# 2019-NUC029LAN.net
KiCad netlist of a schematic drawn in Altium Designer
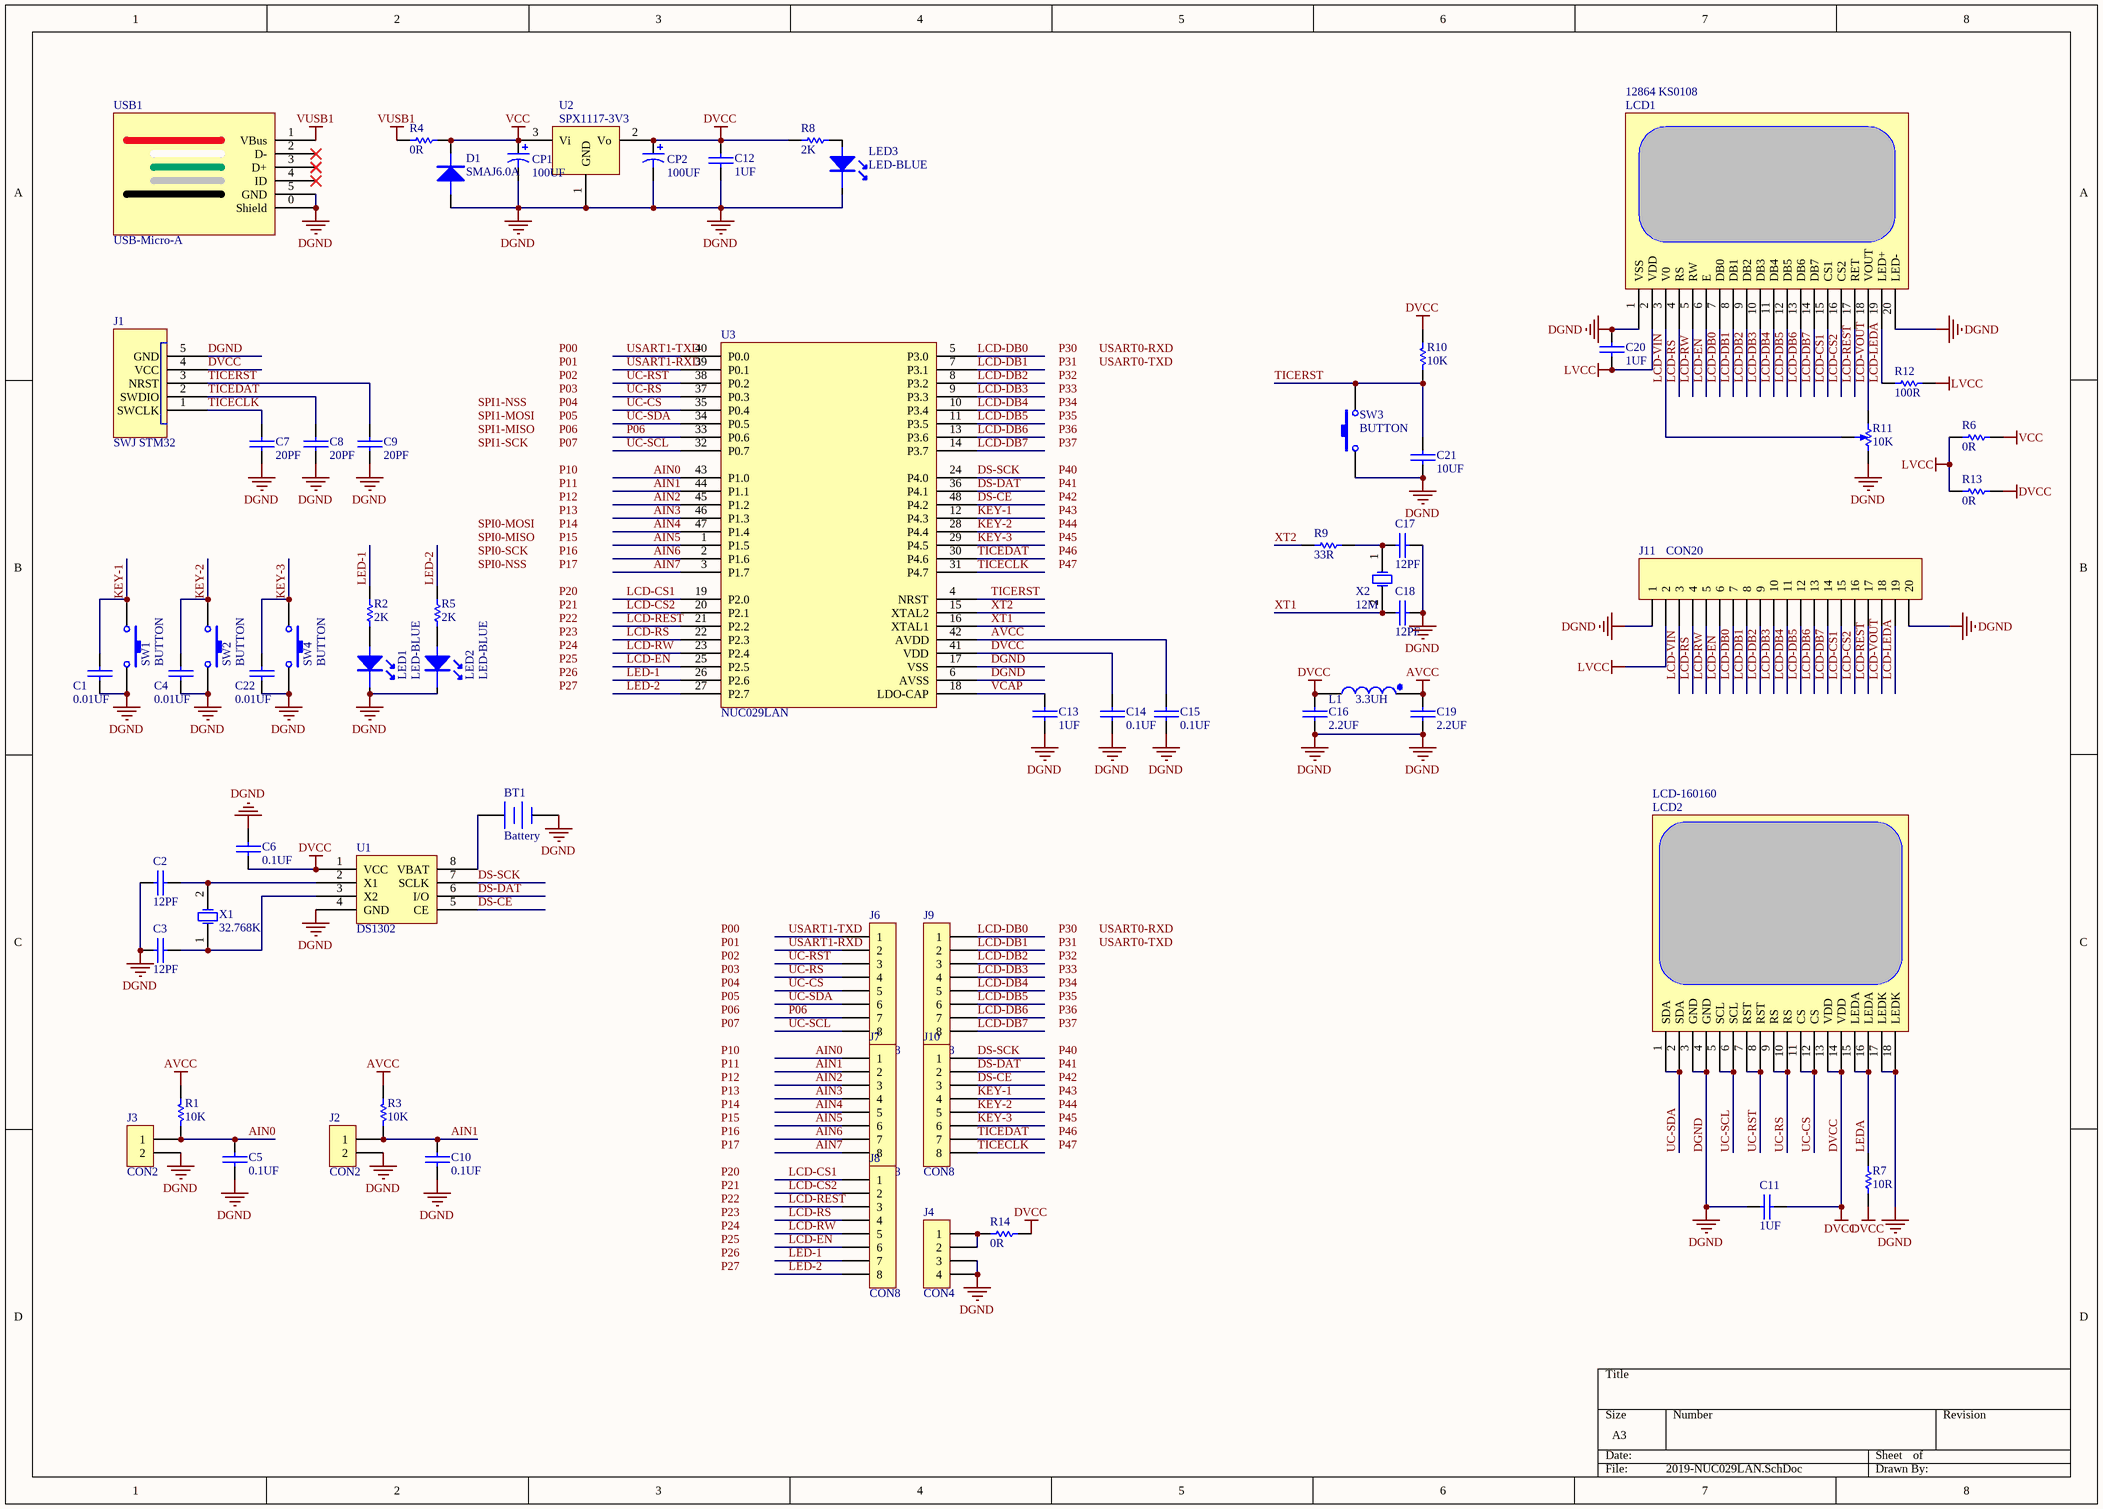
[diagram p0: 2019-NUC029LAN.SchDoc]

(export (version "E")
  (design (tool "Eeschema 10.0.6"))
  (components
    (comp (ref "BT1")
      (value "Battery")
      (footprint "cr1200")
      (description "Multicell Battery")
      (fields (field (name "PUBLISHER") "Altium Limited"))
      (libsource (lib "Miscellaneous Devices") (part "Battery"))
    )
    (comp (ref "C1") (value "0.01UF") (footprint "LC-0603-C") (libsource (lib "原理图库") (part "CAP")))
    (comp (ref "C2") (value "12PF") (footprint "LC-0603-C") (libsource (lib "原理图库") (part "CAP")))
    (comp (ref "C3") (value "12PF") (footprint "LC-0603-C") (libsource (lib "原理图库") (part "CAP")))
    (comp (ref "C4") (value "0.01UF") (footprint "LC-0603-C") (libsource (lib "原理图库") (part "CAP")))
    (comp (ref "C5") (value "0.1UF") (footprint "LC-0603-C") (libsource (lib "原理图库") (part "CAP")))
    (comp (ref "C6") (value "0.1UF") (footprint "LC-0603-C") (libsource (lib "原理图库") (part "CAP")))
    (comp (ref "C7") (value "20PF") (footprint "LC-0603-C") (libsource (lib "原理图库") (part "CAP")))
    (comp (ref "C8") (value "20PF") (footprint "LC-0603-C") (libsource (lib "原理图库") (part "CAP")))
    (comp (ref "C9") (value "20PF") (footprint "LC-0603-C") (libsource (lib "原理图库") (part "CAP")))
    (comp (ref "C10") (value "0.1UF") (footprint "LC-0603-C") (libsource (lib "原理图库") (part "CAP")))
    (comp (ref "C11") (value "1UF") (footprint "lc-0805-c") (libsource (lib "") (part "CAP_1")))
    (comp (ref "C12") (value "1UF") (footprint "lc-0805-c") (libsource (lib "") (part "CAP_1")))
    (comp (ref "C13") (value "1UF") (footprint "LC-0603-C") (libsource (lib "原理图库") (part "CAP")))
    (comp (ref "C14") (value "0.1UF") (footprint "LC-0603-C") (libsource (lib "原理图库") (part "CAP")))
    (comp (ref "C15") (value "0.1UF") (footprint "LC-0603-C") (libsource (lib "原理图库") (part "CAP")))
    (comp (ref "C16") (value "2.2UF") (footprint "LC-0603-C") (libsource (lib "原理图库") (part "CAP")))
    (comp (ref "C17") (value "12PF") (footprint "LC-0603-C") (libsource (lib "原理图库") (part "CAP")))
    (comp (ref "C18") (value "12PF") (footprint "LC-0603-C") (libsource (lib "原理图库") (part "CAP")))
    (comp (ref "C19") (value "2.2UF") (footprint "LC-0603-C") (libsource (lib "原理图库") (part "CAP")))
    (comp (ref "C20") (value "1UF") (footprint "lc-0805-c") (libsource (lib "") (part "CAP_1")))
    (comp (ref "C21") (value "10UF") (footprint "LC-0603-C") (libsource (lib "原理图库") (part "CAP")))
    (comp (ref "C22") (value "0.01UF") (footprint "LC-0603-C") (libsource (lib "原理图库") (part "CAP")))
    (comp (ref "CP1") (value "100UF") (footprint "LC-CASE-B_3528") (libsource (lib "原理图库") (part "CAP1")))
    (comp (ref "CP2") (value "100UF") (footprint "LC-CASE-B_3528") (libsource (lib "原理图库") (part "CAP1")))
    (comp (ref "D1")
      (value "SMAJ6.0A")
      (footprint "LC-SMA(DO-214AC)_S3")
      (libsource (lib "原理图库") (part "DIODE"))
    )
    (comp (ref "J1") (value "SWJ STM32") (footprint "ICD2") (libsource (lib "原理图库.坏") (part "SWJ")))
    (comp (ref "J2")
      (value "CON2")
      (footprint "lc-0805-L")
      (description "Connector")
      (libsource (lib "接插件") (part "CON2"))
    )
    (comp (ref "J3")
      (value "CON2")
      (footprint "lc-0805-L")
      (description "Connector")
      (libsource (lib "接插件") (part "CON2"))
    )
    (comp (ref "J4")
      (value "CON4")
      (footprint "sip-4")
      (description "Connector")
      (libsource (lib "接插件") (part "CON4"))
    )
    (comp (ref "J6")
      (value "CON8")
      (footprint "sip-8")
      (description "Connector")
      (libsource (lib "接插件") (part "CON8"))
    )
    (comp (ref "J7")
      (value "CON8")
      (footprint "sip-8")
      (description "Connector")
      (libsource (lib "接插件") (part "CON8"))
    )
    (comp (ref "J8")
      (value "CON8")
      (footprint "sip-8")
      (description "Connector")
      (libsource (lib "接插件") (part "CON8"))
    )
    (comp (ref "J9")
      (value "CON8")
      (footprint "sip-8")
      (description "Connector")
      (libsource (lib "") (part "CON8_1"))
    )
    (comp (ref "J10")
      (value "CON8")
      (footprint "sip-8")
      (description "Connector")
      (libsource (lib "") (part "CON8_1"))
    )
    (comp (ref "J11")
      (value "CON20")
      (footprint "sip-20")
      (description "Connector")
      (libsource (lib "接插件") (part "CON20"))
    )
    (comp (ref "L1") (value "3.3UH") (footprint "lc-0805-L") (libsource (lib "原理图库") (part "INDUCTOR")))
    (comp (ref "LCD1")
      (value "12864 KS0108")
      (footprint "12864 ks0108")
      (libsource (lib "原理图库.坏") (part "12864 KS0108"))
    )
    (comp (ref "LCD2")
      (value "LCD-160160")
      (footprint "lcd-160160")
      (libsource (lib "原理图库.坏") (part "LCD-160160"))
    )
    (comp (ref "LED1") (value "LED-BLUE") (footprint "LC-0805-LED") (libsource (lib "原理图库.坏") (part "LED")))
    (comp (ref "LED2") (value "LED-BLUE") (footprint "LC-0805-LED") (libsource (lib "原理图库.坏") (part "LED")))
    (comp (ref "LED3") (value "LED-BLUE") (footprint "LC-0805-LED") (libsource (lib "原理图库.坏") (part "LED")))
    (comp (ref "R1") (value "10K") (footprint "LC-0603-R") (libsource (lib "原理图库") (part "RES")))
    (comp (ref "R2") (value "2K") (footprint "LC-0603-R") (libsource (lib "原理图库") (part "RES")))
    (comp (ref "R3") (value "10K") (footprint "LC-0603-R") (libsource (lib "原理图库") (part "RES")))
    (comp (ref "R4") (value "0R") (footprint "lc-0805-l") (libsource (lib "原理图库") (part "RES")))
    (comp (ref "R5") (value "2K") (footprint "LC-0603-R") (libsource (lib "原理图库") (part "RES")))
    (comp (ref "R6") (value "0R") (footprint "lc-0805-l") (libsource (lib "原理图库") (part "RES")))
    (comp (ref "R7") (value "10R") (footprint "lc-0805-r") (libsource (lib "原理图库") (part "RES")))
    (comp (ref "R8") (value "2K") (footprint "LC-0603-R") (libsource (lib "原理图库") (part "RES")))
    (comp (ref "R9") (value "33R") (footprint "LC-0603-R") (libsource (lib "原理图库") (part "RES")))
    (comp (ref "R10") (value "10K") (footprint "LC-0603-R") (libsource (lib "原理图库") (part "RES")))
    (comp (ref "R11") (value "10K") (footprint "dwq-4") (libsource (lib "原理图库.坏") (part "RES-ADJ")))
    (comp (ref "R12") (value "100R") (footprint "lc-0805-r") (libsource (lib "原理图库") (part "RES")))
    (comp (ref "R13") (value "0R") (footprint "lc-0805-l") (libsource (lib "原理图库") (part "RES")))
    (comp (ref "R14") (value "0R") (footprint "lc-0805-l") (libsource (lib "原理图库") (part "RES")))
    (comp (ref "SW1") (value "BUTTON") (footprint "button-c") (libsource (lib "原理图库.坏") (part "BUTTON")))
    (comp (ref "SW2") (value "BUTTON") (footprint "button-c") (libsource (lib "原理图库.坏") (part "BUTTON")))
    (comp (ref "SW3") (value "BUTTON") (footprint "button5") (libsource (lib "原理图库.坏") (part "BUTTON")))
    (comp (ref "SW4") (value "BUTTON") (footprint "button-c") (libsource (lib "原理图库.坏") (part "BUTTON")))
    (comp (ref "U1") (value "DS1302") (footprint "stc-dip8") (libsource (lib "原理图库.坏") (part "DS1302")))
    (comp (ref "U2")
      (value "SPX1117-3V3")
      (footprint "lc-SOT-223")
      (libsource (lib "原理图库.坏") (part "AMS1117"))
    )
    (comp (ref "U3")
      (value "NUC029LAN")
      (footprint "LC-LQFP-48_7x7x05P")
      (libsource (lib "原理图库.坏") (part "NUC029LAN"))
    )
    (comp (ref "USB1")
      (value "USB-Micro-A")
      (footprint "USB-MICRO-R")
      (libsource (lib "USBSch") (part "USB-Micro-A"))
    )
    (comp (ref "X1") (value "32.768K") (footprint "xl-2") (libsource (lib "原理图库") (part "JZ")))
    (comp (ref "X2") (value "12M") (footprint "xl-1") (libsource (lib "原理图库") (part "JZ")))
  )
  (nets
    (net (code "1") (name "/AIN0") (class "Default")
      (node (ref "C5") (pin "2") (pinfunction "2_2") (pintype "passive"))
      (node (ref "J3") (pin "1") (pinfunction "1_1") (pintype "passive"))
      (node (ref "J7") (pin "1") (pinfunction "1_1") (pintype "passive"))
      (node (ref "R1") (pin "2") (pinfunction "2_2") (pintype "passive"))
      (node (ref "U3") (pin "43") (pinfunction "P1.0_43") (pintype "passive"))
    )
    (net (code "2") (name "/AIN1") (class "Default")
      (node (ref "C10") (pin "2") (pinfunction "2_2") (pintype "passive"))
      (node (ref "J2") (pin "1") (pinfunction "1_1") (pintype "passive"))
      (node (ref "J7") (pin "2") (pinfunction "2_2") (pintype "passive"))
      (node (ref "R3") (pin "2") (pinfunction "2_2") (pintype "passive"))
      (node (ref "U3") (pin "44") (pinfunction "P1.1_44") (pintype "passive"))
    )
    (net (code "3") (name "/AIN2") (class "Default")
      (node (ref "J7") (pin "3") (pinfunction "3_3") (pintype "passive"))
      (node (ref "U3") (pin "45") (pinfunction "P1.2_45") (pintype "passive"))
    )
    (net (code "4") (name "/AIN3") (class "Default")
      (node (ref "J7") (pin "4") (pinfunction "4_4") (pintype "passive"))
      (node (ref "U3") (pin "46") (pinfunction "P1.3_46") (pintype "passive"))
    )
    (net (code "5") (name "/AIN4") (class "Default")
      (node (ref "J7") (pin "5") (pinfunction "5_5") (pintype "passive"))
      (node (ref "U3") (pin "47") (pinfunction "P1.4_47") (pintype "passive"))
    )
    (net (code "6") (name "/AIN5") (class "Default")
      (node (ref "J7") (pin "6") (pinfunction "6_6") (pintype "passive"))
      (node (ref "U3") (pin "1") (pinfunction "P1.5_1") (pintype "passive"))
    )
    (net (code "7") (name "/AIN6") (class "Default")
      (node (ref "J7") (pin "7") (pinfunction "7_7") (pintype "passive"))
      (node (ref "U3") (pin "2") (pinfunction "P1.6_2") (pintype "passive"))
    )
    (net (code "8") (name "/AIN7") (class "Default")
      (node (ref "J7") (pin "8") (pinfunction "8_8") (pintype "passive"))
      (node (ref "U3") (pin "3") (pinfunction "P1.7_3") (pintype "passive"))
    )
    (net (code "9") (name "/DS-CE") (class "Default")
      (node (ref "J10") (pin "3") (pinfunction "3_3") (pintype "passive"))
      (node (ref "U1") (pin "5") (pinfunction "CE_5") (pintype "passive"))
      (node (ref "U3") (pin "48") (pinfunction "P4.2_48") (pintype "passive"))
    )
    (net (code "10") (name "/DS-DAT") (class "Default")
      (node (ref "J10") (pin "2") (pinfunction "2_2") (pintype "passive"))
      (node (ref "U1") (pin "6") (pinfunction "I/O_6") (pintype "passive"))
      (node (ref "U3") (pin "36") (pinfunction "P4.1_36") (pintype "passive"))
    )
    (net (code "11") (name "/DS-SCK") (class "Default")
      (node (ref "J10") (pin "1") (pinfunction "1_1") (pintype "passive"))
      (node (ref "U1") (pin "7") (pinfunction "SCLK_7") (pintype "passive"))
      (node (ref "U3") (pin "24") (pinfunction "P4.0_24") (pintype "passive"))
    )
    (net (code "12") (name "/KEY-1") (class "Default")
      (node (ref "C1") (pin "2") (pinfunction "2_2") (pintype "passive"))
      (node (ref "J10") (pin "4") (pinfunction "4_4") (pintype "passive"))
      (node (ref "SW1") (pin "2") (pinfunction "2_2") (pintype "passive"))
      (node (ref "U3") (pin "12") (pinfunction "P4.3_12") (pintype "passive"))
    )
    (net (code "13") (name "/KEY-2") (class "Default")
      (node (ref "C4") (pin "2") (pinfunction "2_2") (pintype "passive"))
      (node (ref "J10") (pin "5") (pinfunction "5_5") (pintype "passive"))
      (node (ref "SW2") (pin "2") (pinfunction "2_2") (pintype "passive"))
      (node (ref "U3") (pin "28") (pinfunction "P4.4_28") (pintype "passive"))
    )
    (net (code "14") (name "/KEY-3") (class "Default")
      (node (ref "C22") (pin "2") (pinfunction "2_2") (pintype "passive"))
      (node (ref "J10") (pin "6") (pinfunction "6_6") (pintype "passive"))
      (node (ref "SW4") (pin "2") (pinfunction "2_2") (pintype "passive"))
      (node (ref "U3") (pin "29") (pinfunction "P4.5_29") (pintype "passive"))
    )
    (net (code "15") (name "/LCD-CS1") (class "Default")
      (node (ref "J11") (pin "15") (pinfunction "15_15") (pintype "passive"))
      (node (ref "J8") (pin "1") (pinfunction "1_1") (pintype "passive"))
      (node (ref "LCD1") (pin "15") (pinfunction "CS1_15") (pintype "passive"))
      (node (ref "U3") (pin "19") (pinfunction "P2.0_19") (pintype "passive"))
    )
    (net (code "16") (name "/LCD-CS2") (class "Default")
      (node (ref "J11") (pin "16") (pinfunction "16_16") (pintype "passive"))
      (node (ref "J8") (pin "2") (pinfunction "2_2") (pintype "passive"))
      (node (ref "LCD1") (pin "16") (pinfunction "CS2_16") (pintype "passive"))
      (node (ref "U3") (pin "20") (pinfunction "P2.1_20") (pintype "passive"))
    )
    (net (code "17") (name "/LCD-DB0") (class "Default")
      (node (ref "J11") (pin "7") (pinfunction "7_7") (pintype "passive"))
      (node (ref "J9") (pin "1") (pinfunction "1_1") (pintype "passive"))
      (node (ref "LCD1") (pin "7") (pinfunction "DB0_7") (pintype "passive"))
      (node (ref "U3") (pin "5") (pinfunction "P3.0_5") (pintype "passive"))
    )
    (net (code "18") (name "/LCD-DB1") (class "Default")
      (node (ref "J11") (pin "8") (pinfunction "8_8") (pintype "passive"))
      (node (ref "J9") (pin "2") (pinfunction "2_2") (pintype "passive"))
      (node (ref "LCD1") (pin "8") (pinfunction "DB1_8") (pintype "passive"))
      (node (ref "U3") (pin "7") (pinfunction "P3.1_7") (pintype "passive"))
    )
    (net (code "19") (name "/LCD-DB2") (class "Default")
      (node (ref "J11") (pin "9") (pinfunction "9_9") (pintype "passive"))
      (node (ref "J9") (pin "3") (pinfunction "3_3") (pintype "passive"))
      (node (ref "LCD1") (pin "9") (pinfunction "DB2_9") (pintype "passive"))
      (node (ref "U3") (pin "8") (pinfunction "P3.2_8") (pintype "passive"))
    )
    (net (code "20") (name "/LCD-DB3") (class "Default")
      (node (ref "J11") (pin "10") (pinfunction "10_10") (pintype "passive"))
      (node (ref "J9") (pin "4") (pinfunction "4_4") (pintype "passive"))
      (node (ref "LCD1") (pin "10") (pinfunction "DB3_10") (pintype "passive"))
      (node (ref "U3") (pin "9") (pinfunction "P3.3_9") (pintype "passive"))
    )
    (net (code "21") (name "/LCD-DB4") (class "Default")
      (node (ref "J11") (pin "11") (pinfunction "11_11") (pintype "passive"))
      (node (ref "J9") (pin "5") (pinfunction "5_5") (pintype "passive"))
      (node (ref "LCD1") (pin "11") (pinfunction "DB4_11") (pintype "passive"))
      (node (ref "U3") (pin "10") (pinfunction "P3.4_10") (pintype "passive"))
    )
    (net (code "22") (name "/LCD-DB5") (class "Default")
      (node (ref "J11") (pin "12") (pinfunction "12_12") (pintype "passive"))
      (node (ref "J9") (pin "6") (pinfunction "6_6") (pintype "passive"))
      (node (ref "LCD1") (pin "12") (pinfunction "DB5_12") (pintype "passive"))
      (node (ref "U3") (pin "11") (pinfunction "P3.5_11") (pintype "passive"))
    )
    (net (code "23") (name "/LCD-DB6") (class "Default")
      (node (ref "J11") (pin "13") (pinfunction "13_13") (pintype "passive"))
      (node (ref "J9") (pin "7") (pinfunction "7_7") (pintype "passive"))
      (node (ref "LCD1") (pin "13") (pinfunction "DB6_13") (pintype "passive"))
      (node (ref "U3") (pin "13") (pinfunction "P3.6_13") (pintype "passive"))
    )
    (net (code "24") (name "/LCD-DB7") (class "Default")
      (node (ref "J11") (pin "14") (pinfunction "14_14") (pintype "passive"))
      (node (ref "J9") (pin "8") (pinfunction "8_8") (pintype "passive"))
      (node (ref "LCD1") (pin "14") (pinfunction "DB7_14") (pintype "passive"))
      (node (ref "U3") (pin "14") (pinfunction "P3.7_14") (pintype "passive"))
    )
    (net (code "25") (name "/LCD-EN") (class "Default")
      (node (ref "J11") (pin "6") (pinfunction "6_6") (pintype "passive"))
      (node (ref "J8") (pin "6") (pinfunction "6_6") (pintype "passive"))
      (node (ref "LCD1") (pin "6") (pinfunction "E_6") (pintype "passive"))
      (node (ref "U3") (pin "25") (pinfunction "P2.5_25") (pintype "passive"))
    )
    (net (code "26") (name "/LCD-LEDA") (class "Default")
      (node (ref "J11") (pin "19") (pinfunction "19_19") (pintype "passive"))
      (node (ref "LCD1") (pin "19") (pinfunction "LED+_19") (pintype "passive"))
      (node (ref "R12") (pin "1") (pinfunction "1_1") (pintype "passive"))
    )
    (net (code "27") (name "/LCD-REST") (class "Default")
      (node (ref "J11") (pin "17") (pinfunction "17_17") (pintype "passive"))
      (node (ref "J8") (pin "3") (pinfunction "3_3") (pintype "passive"))
      (node (ref "LCD1") (pin "17") (pinfunction "RET_17") (pintype "passive"))
      (node (ref "U3") (pin "21") (pinfunction "P2.2_21") (pintype "passive"))
    )
    (net (code "28") (name "/LCD-RS") (class "Default")
      (node (ref "J11") (pin "4") (pinfunction "4_4") (pintype "passive"))
      (node (ref "J8") (pin "4") (pinfunction "4_4") (pintype "passive"))
      (node (ref "LCD1") (pin "4") (pinfunction "RS_4") (pintype "passive"))
      (node (ref "U3") (pin "22") (pinfunction "P2.3_22") (pintype "passive"))
    )
    (net (code "29") (name "/LCD-RW") (class "Default")
      (node (ref "J11") (pin "5") (pinfunction "5_5") (pintype "passive"))
      (node (ref "J8") (pin "5") (pinfunction "5_5") (pintype "passive"))
      (node (ref "LCD1") (pin "5") (pinfunction "RW_5") (pintype "passive"))
      (node (ref "U3") (pin "23") (pinfunction "P2.4_23") (pintype "passive"))
    )
    (net (code "30") (name "/LCD-VIN") (class "Default")
      (node (ref "J11") (pin "3") (pinfunction "3_3") (pintype "passive"))
      (node (ref "LCD1") (pin "3") (pinfunction "V0_3") (pintype "passive"))
      (node (ref "R11") (pin "3") (pinfunction "3_3") (pintype "passive"))
    )
    (net (code "31") (name "/LCD-VOUT") (class "Default")
      (node (ref "J11") (pin "18") (pinfunction "18_18") (pintype "passive"))
      (node (ref "LCD1") (pin "18") (pinfunction "VOUT_18") (pintype "passive"))
      (node (ref "R11") (pin "2") (pinfunction "2_2") (pintype "passive"))
    )
    (net (code "32") (name "/LED-1") (class "Default")
      (node (ref "J8") (pin "7") (pinfunction "7_7") (pintype "passive"))
      (node (ref "R2") (pin "1") (pinfunction "1_1") (pintype "passive"))
      (node (ref "U3") (pin "26") (pinfunction "P2.6_26") (pintype "passive"))
    )
    (net (code "33") (name "/LED-2") (class "Default")
      (node (ref "J8") (pin "8") (pinfunction "8_8") (pintype "passive"))
      (node (ref "R5") (pin "1") (pinfunction "1_1") (pintype "passive"))
      (node (ref "U3") (pin "27") (pinfunction "P2.7_27") (pintype "passive"))
    )
    (net (code "34") (name "/LEDA") (class "Default")
      (node (ref "LCD2") (pin "15") (pinfunction "LEDA_15") (pintype "passive"))
      (node (ref "LCD2") (pin "16") (pinfunction "LEDA_16") (pintype "passive"))
      (node (ref "R7") (pin "2") (pinfunction "2_2") (pintype "passive"))
    )
    (net (code "41") (name "/P06") (class "Default")
      (node (ref "J6") (pin "7") (pinfunction "7_7") (pintype "passive"))
      (node (ref "U3") (pin "33") (pinfunction "P0.6_33") (pintype "passive"))
    )
    (net (code "83") (name "/TICECLK") (class "Default")
      (node (ref "C7") (pin "2") (pinfunction "2_2") (pintype "passive"))
      (node (ref "J1") (pin "1") (pinfunction "SWCLK_1") (pintype "passive"))
      (node (ref "J10") (pin "8") (pinfunction "8_8") (pintype "passive"))
      (node (ref "U3") (pin "31") (pinfunction "P4.7_31") (pintype "passive"))
    )
    (net (code "84") (name "/TICEDAT") (class "Default")
      (node (ref "C8") (pin "2") (pinfunction "2_2") (pintype "passive"))
      (node (ref "J1") (pin "2") (pinfunction "SWDIO_2") (pintype "passive"))
      (node (ref "J10") (pin "7") (pinfunction "7_7") (pintype "passive"))
      (node (ref "U3") (pin "30") (pinfunction "P4.6_30") (pintype "passive"))
    )
    (net (code "85") (name "/TICERST") (class "Default")
      (node (ref "C21") (pin "1") (pinfunction "1_1") (pintype "passive"))
      (node (ref "C9") (pin "2") (pinfunction "2_2") (pintype "passive"))
      (node (ref "J1") (pin "3") (pinfunction "NRST_3") (pintype "passive"))
      (node (ref "R10") (pin "2") (pinfunction "2_2") (pintype "passive"))
      (node (ref "SW3") (pin "2") (pinfunction "2_2") (pintype "passive"))
      (node (ref "U3") (pin "4") (pinfunction "NRST_4") (pintype "passive"))
    )
    (net (code "86") (name "/UC-CS") (class "Default")
      (node (ref "J6") (pin "5") (pinfunction "5_5") (pintype "passive"))
      (node (ref "LCD2") (pin "11") (pinfunction "CS_11") (pintype "passive"))
      (node (ref "LCD2") (pin "12") (pinfunction "CS_12") (pintype "passive"))
      (node (ref "U3") (pin "35") (pinfunction "P0.4_35") (pintype "passive"))
    )
    (net (code "87") (name "/UC-RS") (class "Default")
      (node (ref "J6") (pin "4") (pinfunction "4_4") (pintype "passive"))
      (node (ref "LCD2") (pin "10") (pinfunction "RS_10") (pintype "passive"))
      (node (ref "LCD2") (pin "9") (pinfunction "RS_9") (pintype "passive"))
      (node (ref "U3") (pin "37") (pinfunction "P0.3_37") (pintype "passive"))
    )
    (net (code "88") (name "/UC-RST") (class "Default")
      (node (ref "J6") (pin "3") (pinfunction "3_3") (pintype "passive"))
      (node (ref "LCD2") (pin "7") (pinfunction "RST_7") (pintype "passive"))
      (node (ref "LCD2") (pin "8") (pinfunction "RST_8") (pintype "passive"))
      (node (ref "U3") (pin "38") (pinfunction "P0.2_38") (pintype "passive"))
    )
    (net (code "89") (name "/UC-SCL") (class "Default")
      (node (ref "J6") (pin "8") (pinfunction "8_8") (pintype "passive"))
      (node (ref "LCD2") (pin "5") (pinfunction "SCL_5") (pintype "passive"))
      (node (ref "LCD2") (pin "6") (pinfunction "SCL_6") (pintype "passive"))
      (node (ref "U3") (pin "32") (pinfunction "P0.7_32") (pintype "passive"))
    )
    (net (code "90") (name "/UC-SDA") (class "Default")
      (node (ref "J6") (pin "6") (pinfunction "6_6") (pintype "passive"))
      (node (ref "LCD2") (pin "1") (pinfunction "SDA_1") (pintype "passive"))
      (node (ref "LCD2") (pin "2") (pinfunction "SDA_2") (pintype "passive"))
      (node (ref "U3") (pin "34") (pinfunction "P0.5_34") (pintype "passive"))
    )
    (net (code "93") (name "/USART1-RXD") (class "Default")
      (node (ref "J6") (pin "2") (pinfunction "2_2") (pintype "passive"))
      (node (ref "U3") (pin "39") (pinfunction "P0.1_39") (pintype "passive"))
    )
    (net (code "94") (name "/USART1-TXD") (class "Default")
      (node (ref "J6") (pin "1") (pinfunction "1_1") (pintype "passive"))
      (node (ref "U3") (pin "40") (pinfunction "P0.0_40") (pintype "passive"))
    )
    (net (code "95") (name "/VCAP") (class "Default")
      (node (ref "C13") (pin "1") (pinfunction "1_1") (pintype "passive"))
      (node (ref "U3") (pin "18") (pinfunction "LDO-CAP_18") (pintype "passive"))
    )
    (net (code "96") (name "/XT1") (class "Default")
      (node (ref "C18") (pin "1") (pinfunction "1_1") (pintype "passive"))
      (node (ref "U3") (pin "16") (pinfunction "XTAL1_16") (pintype "passive"))
      (node (ref "X2") (pin "2") (pinfunction "2_2") (pintype "passive"))
    )
    (net (code "97") (name "/XT2") (class "Default")
      (node (ref "R9") (pin "1") (pinfunction "1_1") (pintype "passive"))
      (node (ref "U3") (pin "15") (pinfunction "XTAL2_15") (pintype "passive"))
    )
    (net (code "98") (name "AVCC") (class "Default")
      (node (ref "C15") (pin "2") (pinfunction "2_2") (pintype "passive"))
      (node (ref "C19") (pin "2") (pinfunction "2_2") (pintype "passive"))
      (node (ref "L1") (pin "1") (pinfunction "1_1") (pintype "passive"))
      (node (ref "R1") (pin "1") (pinfunction "1_1") (pintype "passive"))
      (node (ref "R3") (pin "1") (pinfunction "1_1") (pintype "passive"))
      (node (ref "U3") (pin "42") (pinfunction "AVDD_42") (pintype "passive"))
    )
    (net (code "99") (name "DGND") (class "Default")
      (node (ref "BT1") (pin "2") (pinfunction "-_2") (pintype "passive"))
      (node (ref "C1") (pin "1") (pinfunction "1_1") (pintype "passive"))
      (node (ref "C10") (pin "1") (pinfunction "1_1") (pintype "passive"))
      (node (ref "C11") (pin "1") (pinfunction "1_1") (pintype "passive"))
      (node (ref "C12") (pin "2") (pinfunction "2_2") (pintype "passive"))
      (node (ref "C13") (pin "2") (pinfunction "2_2") (pintype "passive"))
      (node (ref "C14") (pin "1") (pinfunction "1_1") (pintype "passive"))
      (node (ref "C15") (pin "1") (pinfunction "1_1") (pintype "passive"))
      (node (ref "C16") (pin "2") (pinfunction "2_2") (pintype "passive"))
      (node (ref "C17") (pin "2") (pinfunction "2_2") (pintype "passive"))
      (node (ref "C18") (pin "2") (pinfunction "2_2") (pintype "passive"))
      (node (ref "C19") (pin "1") (pinfunction "1_1") (pintype "passive"))
      (node (ref "C2") (pin "1") (pinfunction "1_1") (pintype "passive"))
      (node (ref "C20") (pin "1") (pinfunction "1_1") (pintype "passive"))
      (node (ref "C21") (pin "2") (pinfunction "2_2") (pintype "passive"))
      (node (ref "C22") (pin "1") (pinfunction "1_1") (pintype "passive"))
      (node (ref "C3") (pin "1") (pinfunction "1_1") (pintype "passive"))
      (node (ref "C4") (pin "1") (pinfunction "1_1") (pintype "passive"))
      (node (ref "C5") (pin "1") (pinfunction "1_1") (pintype "passive"))
      (node (ref "C6") (pin "2") (pinfunction "2_2") (pintype "passive"))
      (node (ref "C7") (pin "1") (pinfunction "1_1") (pintype "passive"))
      (node (ref "C8") (pin "1") (pinfunction "1_1") (pintype "passive"))
      (node (ref "C9") (pin "1") (pinfunction "1_1") (pintype "passive"))
      (node (ref "CP1") (pin "2") (pinfunction "2_2") (pintype "passive"))
      (node (ref "CP2") (pin "2") (pinfunction "2_2") (pintype "passive"))
      (node (ref "D1") (pin "1") (pinfunction "1_1") (pintype "passive"))
      (node (ref "J1") (pin "5") (pinfunction "GND_5") (pintype "passive"))
      (node (ref "J11") (pin "1") (pinfunction "1_1") (pintype "passive"))
      (node (ref "J11") (pin "20") (pinfunction "20_20") (pintype "passive"))
      (node (ref "J2") (pin "2") (pinfunction "2_2") (pintype "passive"))
      (node (ref "J3") (pin "2") (pinfunction "2_2") (pintype "passive"))
      (node (ref "J4") (pin "3") (pinfunction "3_3") (pintype "passive"))
      (node (ref "J4") (pin "4") (pinfunction "4_4") (pintype "passive"))
      (node (ref "LCD1") (pin "1") (pinfunction "VSS_1") (pintype "passive"))
      (node (ref "LCD1") (pin "20") (pinfunction "LED-_20") (pintype "passive"))
      (node (ref "LCD2") (pin "17") (pinfunction "LEDK_17") (pintype "passive"))
      (node (ref "LCD2") (pin "18") (pinfunction "LEDK_18") (pintype "passive"))
      (node (ref "LCD2") (pin "3") (pinfunction "GND_3") (pintype "passive"))
      (node (ref "LCD2") (pin "4") (pinfunction "GND_4") (pintype "passive"))
      (node (ref "LED1") (pin "K") (pinfunction "K_K") (pintype "passive"))
      (node (ref "LED2") (pin "K") (pinfunction "K_K") (pintype "passive"))
      (node (ref "LED3") (pin "K") (pinfunction "K_K") (pintype "passive"))
      (node (ref "R11") (pin "1") (pinfunction "1_1") (pintype "passive"))
      (node (ref "SW1") (pin "1") (pinfunction "1_1") (pintype "passive"))
      (node (ref "SW2") (pin "1") (pinfunction "1_1") (pintype "passive"))
      (node (ref "SW3") (pin "1") (pinfunction "1_1") (pintype "passive"))
      (node (ref "SW4") (pin "1") (pinfunction "1_1") (pintype "passive"))
      (node (ref "U1") (pin "4") (pinfunction "GND_4") (pintype "passive"))
      (node (ref "U2") (pin "1") (pinfunction "GND_1") (pintype "passive"))
      (node (ref "U3") (pin "17") (pinfunction "VSS_17") (pintype "passive"))
      (node (ref "U3") (pin "6") (pinfunction "AVSS_6") (pintype "passive"))
      (node (ref "USB1") (pin "0") (pinfunction "Shield_0") (pintype "passive"))
      (node (ref "USB1") (pin "5") (pinfunction "GND_5") (pintype "passive"))
    )
    (net (code "100") (name "DVCC") (class "Default")
      (node (ref "C11") (pin "2") (pinfunction "2_2") (pintype "passive"))
      (node (ref "C12") (pin "1") (pinfunction "1_1") (pintype "passive"))
      (node (ref "C14") (pin "2") (pinfunction "2_2") (pintype "passive"))
      (node (ref "C16") (pin "1") (pinfunction "1_1") (pintype "passive"))
      (node (ref "C6") (pin "1") (pinfunction "1_1") (pintype "passive"))
      (node (ref "CP2") (pin "1") (pinfunction "1_1") (pintype "passive"))
      (node (ref "J1") (pin "4") (pinfunction "VCC_4") (pintype "passive"))
      (node (ref "L1") (pin "2") (pinfunction "2_2") (pintype "passive"))
      (node (ref "LCD2") (pin "13") (pinfunction "VDD_13") (pintype "passive"))
      (node (ref "LCD2") (pin "14") (pinfunction "VDD_14") (pintype "passive"))
      (node (ref "R10") (pin "1") (pinfunction "1_1") (pintype "passive"))
      (node (ref "R13") (pin "2") (pinfunction "2_2") (pintype "passive"))
      (node (ref "R14") (pin "2") (pinfunction "2_2") (pintype "passive"))
      (node (ref "R7") (pin "1") (pinfunction "1_1") (pintype "passive"))
      (node (ref "R8") (pin "2") (pinfunction "2_2") (pintype "passive"))
      (node (ref "U1") (pin "1") (pinfunction "VCC_1") (pintype "passive"))
      (node (ref "U2") (pin "2") (pinfunction "Vo_2") (pintype "passive"))
      (node (ref "U3") (pin "41") (pinfunction "VDD_41") (pintype "passive"))
    )
    (net (code "101") (name "LVCC") (class "Default")
      (node (ref "C20") (pin "2") (pinfunction "2_2") (pintype "passive"))
      (node (ref "J11") (pin "2") (pinfunction "2_2") (pintype "passive"))
      (node (ref "LCD1") (pin "2") (pinfunction "VDD_2") (pintype "passive"))
      (node (ref "R12") (pin "2") (pinfunction "2_2") (pintype "passive"))
      (node (ref "R13") (pin "1") (pinfunction "1_1") (pintype "passive"))
      (node (ref "R6") (pin "1") (pinfunction "1_1") (pintype "passive"))
    )
    (net (code "102") (name "Net-(BT1-+)") (class "Default")
      (node (ref "BT1") (pin "1") (pinfunction "+_1") (pintype "passive"))
      (node (ref "U1") (pin "8") (pinfunction "VBAT_8") (pintype "passive"))
    )
    (net (code "103") (name "Net-(C17-Pad1)") (class "Default")
      (node (ref "C17") (pin "1") (pinfunction "1_1") (pintype "passive"))
      (node (ref "R9") (pin "2") (pinfunction "2_2") (pintype "passive"))
      (node (ref "X2") (pin "1") (pinfunction "1_1") (pintype "passive"))
    )
    (net (code "104") (name "Net-(J4-Pad1)") (class "Default")
      (node (ref "J4") (pin "1") (pinfunction "1_1") (pintype "passive"))
      (node (ref "J4") (pin "2") (pinfunction "2_2") (pintype "passive"))
      (node (ref "R14") (pin "1") (pinfunction "1_1") (pintype "passive"))
    )
    (net (code "105") (name "Net-(LED1-PadA)") (class "Default")
      (node (ref "LED1") (pin "A") (pinfunction "A_A") (pintype "passive"))
      (node (ref "R2") (pin "2") (pinfunction "2_2") (pintype "passive"))
    )
    (net (code "106") (name "Net-(LED2-PadA)") (class "Default")
      (node (ref "LED2") (pin "A") (pinfunction "A_A") (pintype "passive"))
      (node (ref "R5") (pin "2") (pinfunction "2_2") (pintype "passive"))
    )
    (net (code "107") (name "Net-(LED3-PadA)") (class "Default")
      (node (ref "LED3") (pin "A") (pinfunction "A_A") (pintype "passive"))
      (node (ref "R8") (pin "1") (pinfunction "1_1") (pintype "passive"))
    )
    (net (code "108") (name "Net-(U1-X1)") (class "Default")
      (node (ref "C2") (pin "2") (pinfunction "2_2") (pintype "passive"))
      (node (ref "U1") (pin "2") (pinfunction "X1_2") (pintype "passive"))
      (node (ref "X1") (pin "2") (pinfunction "2_2") (pintype "passive"))
    )
    (net (code "109") (name "Net-(U1-X2)") (class "Default")
      (node (ref "C3") (pin "2") (pinfunction "2_2") (pintype "passive"))
      (node (ref "U1") (pin "3") (pinfunction "X2_3") (pintype "passive"))
      (node (ref "X1") (pin "1") (pinfunction "1_1") (pintype "passive"))
    )
    (net (code "110") (name "VCC") (class "Default")
      (node (ref "CP1") (pin "1") (pinfunction "1_1") (pintype "passive"))
      (node (ref "D1") (pin "2") (pinfunction "2_2") (pintype "passive"))
      (node (ref "R4") (pin "2") (pinfunction "2_2") (pintype "passive"))
      (node (ref "R6") (pin "2") (pinfunction "2_2") (pintype "passive"))
      (node (ref "U2") (pin "3") (pinfunction "Vi_3") (pintype "passive"))
    )
    (net (code "111") (name "VUSB1") (class "Default")
      (node (ref "R4") (pin "1") (pinfunction "1_1") (pintype "passive"))
      (node (ref "USB1") (pin "1") (pinfunction "VBus_1") (pintype "passive"))
    )
    (net (code "112") (name "unconnected-(USB1-D+-Pad3)") (class "Default")
      (node (ref "USB1") (pin "3") (pinfunction "D+_3") (pintype "passive+no_connect"))
    )
    (net (code "113") (name "unconnected-(USB1-D--Pad2)") (class "Default")
      (node (ref "USB1") (pin "2") (pinfunction "D-_2") (pintype "passive+no_connect"))
    )
    (net (code "114") (name "unconnected-(USB1-ID-Pad4)") (class "Default")
      (node (ref "USB1") (pin "4") (pinfunction "ID_4") (pintype "passive+no_connect"))
    )
  )
)
